# work.net
KiCad netlist of a schematic drawn in EAGLE
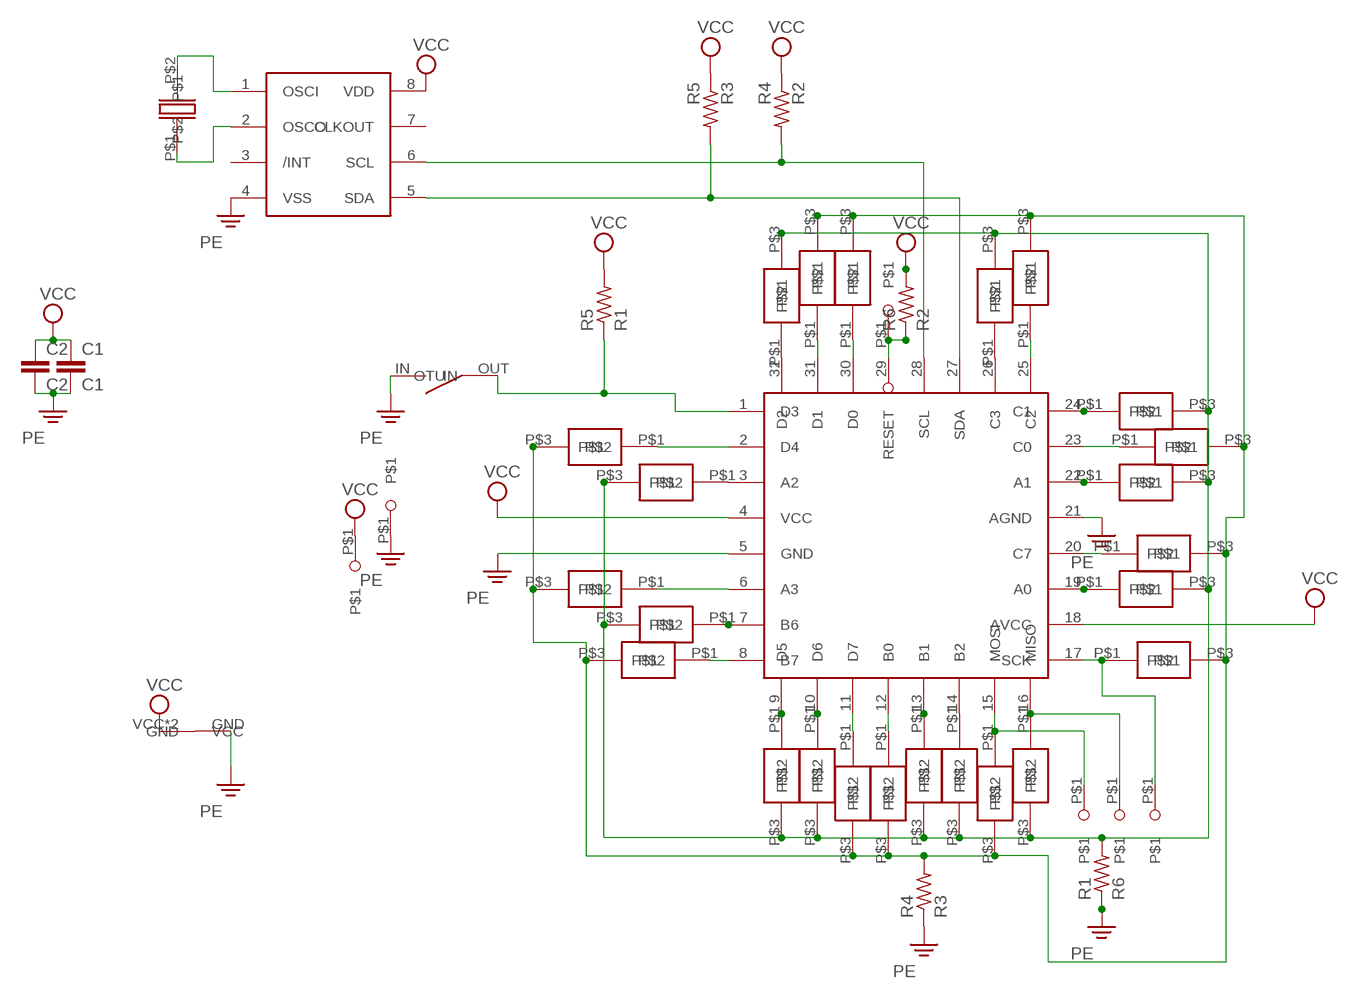
[diagram p0: schematic, sheet 1]

(export (version "E")
  (design (tool "Eeschema 10.0.6"))
  (components
    (comp (ref "C1")
      (value "C1")
      (footprint "eagle-import:C0805K")
      (libsource (lib "eagle-import") (part "C-EUC0805K"))
    )
    (comp (ref "C2")
      (value "C2")
      (footprint "eagle-import:C0805K")
      (libsource (lib "eagle-import") (part "C-EUC0805K"))
    )
    (comp (ref "R1")
      (value "R6")
      (footprint "eagle-import:R0805")
      (libsource (lib "eagle-import") (part "R-US_R0805"))
    )
    (comp (ref "R2")
      (value "R4")
      (footprint "eagle-import:R0805")
      (libsource (lib "eagle-import") (part "R-US_R0805"))
    )
    (comp (ref "R3")
      (value "R5")
      (footprint "eagle-import:R0805")
      (libsource (lib "eagle-import") (part "R-US_R0805"))
    )
    (comp (ref "R4")
      (value "R3")
      (footprint "eagle-import:R0805")
      (libsource (lib "eagle-import") (part "R-US_R0805"))
    )
    (comp (ref "R5")
      (value "R1")
      (footprint "eagle-import:R0805")
      (libsource (lib "eagle-import") (part "R-US_R0805"))
    )
    (comp (ref "R6")
      (value "R2")
      (footprint "eagle-import:R0805")
      (libsource (lib "eagle-import") (part "R-US_R0805"))
    )
    (comp (ref "U$1")
      (value "SMDLED")
      (footprint "eagle-import:SMDLED")
      (libsource (lib "eagle-import") (part "SMDLED"))
    )
    (comp (ref "U$2")
      (value "SMDLED")
      (footprint "eagle-import:SMDLED")
      (libsource (lib "eagle-import") (part "SMDLED"))
    )
    (comp (ref "U$3")
      (value "SMDLED")
      (footprint "eagle-import:SMDLED")
      (libsource (lib "eagle-import") (part "SMDLED"))
    )
    (comp (ref "U$4")
      (value "SMDLED")
      (footprint "eagle-import:SMDLED")
      (libsource (lib "eagle-import") (part "SMDLED"))
    )
    (comp (ref "U$5")
      (value "SMDLED")
      (footprint "eagle-import:SMDLED")
      (libsource (lib "eagle-import") (part "SMDLED"))
    )
    (comp (ref "U$6")
      (value "SMDLED")
      (footprint "eagle-import:SMDLED")
      (libsource (lib "eagle-import") (part "SMDLED"))
    )
    (comp (ref "U$7")
      (value "SMDLED")
      (footprint "eagle-import:SMDLED")
      (libsource (lib "eagle-import") (part "SMDLED"))
    )
    (comp (ref "U$8")
      (value "SMDLED")
      (footprint "eagle-import:SMDLED")
      (libsource (lib "eagle-import") (part "SMDLED"))
    )
    (comp (ref "U$9")
      (value "SMDLED")
      (footprint "eagle-import:SMDLED")
      (libsource (lib "eagle-import") (part "SMDLED"))
    )
    (comp (ref "U$10")
      (value "SMDLED")
      (footprint "eagle-import:SMDLED")
      (libsource (lib "eagle-import") (part "SMDLED"))
    )
    (comp (ref "U$11")
      (value "SMDLED")
      (footprint "eagle-import:SMDLED")
      (libsource (lib "eagle-import") (part "SMDLED"))
    )
    (comp (ref "U$12")
      (value "SMDLED")
      (footprint "eagle-import:SMDLED")
      (libsource (lib "eagle-import") (part "SMDLED"))
    )
    (comp (ref "U$13")
      (value "SMDLED")
      (footprint "eagle-import:SMDLED")
      (libsource (lib "eagle-import") (part "SMDLED"))
    )
    (comp (ref "U$14")
      (value "SMDLED")
      (footprint "eagle-import:SMDLED")
      (libsource (lib "eagle-import") (part "SMDLED"))
    )
    (comp (ref "U$15")
      (value "SMDLED")
      (footprint "eagle-import:SMDLED")
      (libsource (lib "eagle-import") (part "SMDLED"))
    )
    (comp (ref "U$16")
      (value "SMDLED")
      (footprint "eagle-import:SMDLED")
      (libsource (lib "eagle-import") (part "SMDLED"))
    )
    (comp (ref "U$17")
      (value "SMDLED")
      (footprint "eagle-import:SMDLED")
      (libsource (lib "eagle-import") (part "SMDLED"))
    )
    (comp (ref "U$18")
      (value "SMDLED")
      (footprint "eagle-import:SMDLED")
      (libsource (lib "eagle-import") (part "SMDLED"))
    )
    (comp (ref "U$19")
      (value "SMDLED")
      (footprint "eagle-import:SMDLED")
      (libsource (lib "eagle-import") (part "SMDLED"))
    )
    (comp (ref "U$20")
      (value "SMDLED")
      (footprint "eagle-import:SMDLED")
      (libsource (lib "eagle-import") (part "SMDLED"))
    )
    (comp (ref "U$21")
      (value "SMDLED")
      (footprint "eagle-import:SMDLED")
      (libsource (lib "eagle-import") (part "SMDLED"))
    )
    (comp (ref "U$22")
      (value "SMDLED")
      (footprint "eagle-import:SMDLED")
      (libsource (lib "eagle-import") (part "SMDLED"))
    )
    (comp (ref "U$23")
      (value "SMDLED")
      (footprint "eagle-import:SMDLED")
      (libsource (lib "eagle-import") (part "SMDLED"))
    )
    (comp (ref "U$24")
      (value "SMDLED")
      (footprint "eagle-import:SMDLED")
      (libsource (lib "eagle-import") (part "SMDLED"))
    )
    (comp (ref "U$25")
      (value "ATTINY88")
      (footprint "eagle-import:32-TQFT")
      (libsource (lib "eagle-import") (part "ATTINY88"))
    )
    (comp (ref "U$26")
      (value "PAD50")
      (footprint "eagle-import:PAD50")
      (libsource (lib "eagle-import") (part "PAD50"))
    )
    (comp (ref "U$27")
      (value "BAT2009")
      (footprint "eagle-import:BAT2009")
      (libsource (lib "eagle-import") (part "BAT2009"))
    )
    (comp (ref "U$28")
      (value "INT2")
      (footprint "eagle-import:INT2")
      (libsource (lib "eagle-import") (part "INT2"))
    )
    (comp (ref "U$29")
      (value "SMDCRYSTAL")
      (footprint "eagle-import:SMDCRYSTAL")
      (libsource (lib "eagle-import") (part "SMDCRYSTAL"))
    )
    (comp (ref "U$30")
      (value "RTC-SOIC")
      (footprint "eagle-import:8-SOIC")
      (libsource (lib "eagle-import") (part "RTC-SOIC"))
    )
    (comp (ref "U$31")
      (value "PAD50")
      (footprint "eagle-import:PAD50")
      (libsource (lib "eagle-import") (part "PAD50"))
    )
    (comp (ref "U$32")
      (value "PAD50")
      (footprint "eagle-import:PAD50")
      (libsource (lib "eagle-import") (part "PAD50"))
    )
    (comp (ref "U$33")
      (value "PAD50")
      (footprint "eagle-import:PAD50")
      (libsource (lib "eagle-import") (part "PAD50"))
    )
    (comp (ref "U$34")
      (value "PAD50")
      (footprint "eagle-import:PAD50")
      (libsource (lib "eagle-import") (part "PAD50"))
    )
    (comp (ref "U$35")
      (value "PAD50")
      (footprint "eagle-import:PAD50")
      (libsource (lib "eagle-import") (part "PAD50"))
    )
  )
  (nets
    (net (code "1") (name "Net-(U$1-P$2)") (class "Default")
      (node (ref "R4") (pin "2") (pinfunction "2_2") (pintype "passive"))
      (node (ref "U$1") (pin "P$3") (pinfunction "P$2_P$3") (pintype "bidirectional"))
      (node (ref "U$10") (pin "P$3") (pinfunction "P$2_P$3") (pintype "bidirectional"))
      (node (ref "U$11") (pin "P$3") (pinfunction "P$2_P$3") (pintype "bidirectional"))
      (node (ref "U$13") (pin "P$3") (pinfunction "P$2_P$3") (pintype "bidirectional"))
      (node (ref "U$15") (pin "P$3") (pinfunction "P$2_P$3") (pintype "bidirectional"))
      (node (ref "U$17") (pin "P$3") (pinfunction "P$2_P$3") (pintype "bidirectional"))
      (node (ref "U$20") (pin "P$3") (pinfunction "P$2_P$3") (pintype "bidirectional"))
      (node (ref "U$22") (pin "P$3") (pinfunction "P$2_P$3") (pintype "bidirectional"))
      (node (ref "U$23") (pin "P$3") (pinfunction "P$2_P$3") (pintype "bidirectional"))
      (node (ref "U$4") (pin "P$3") (pinfunction "P$2_P$3") (pintype "bidirectional"))
      (node (ref "U$8") (pin "P$3") (pinfunction "P$2_P$3") (pintype "bidirectional"))
      (node (ref "U$9") (pin "P$3") (pinfunction "P$2_P$3") (pintype "bidirectional"))
    )
    (net (code "2") (name "Net-(U$12-P$2)") (class "Default")
      (node (ref "R1") (pin "2") (pinfunction "2_2") (pintype "passive"))
      (node (ref "U$12") (pin "P$3") (pinfunction "P$2_P$3") (pintype "bidirectional"))
      (node (ref "U$14") (pin "P$3") (pinfunction "P$2_P$3") (pintype "bidirectional"))
      (node (ref "U$16") (pin "P$3") (pinfunction "P$2_P$3") (pintype "bidirectional"))
      (node (ref "U$18") (pin "P$3") (pinfunction "P$2_P$3") (pintype "bidirectional"))
      (node (ref "U$19") (pin "P$3") (pinfunction "P$2_P$3") (pintype "bidirectional"))
      (node (ref "U$2") (pin "P$3") (pinfunction "P$2_P$3") (pintype "bidirectional"))
      (node (ref "U$21") (pin "P$3") (pinfunction "P$2_P$3") (pintype "bidirectional"))
      (node (ref "U$24") (pin "P$3") (pinfunction "P$2_P$3") (pintype "bidirectional"))
      (node (ref "U$3") (pin "P$3") (pinfunction "P$2_P$3") (pintype "bidirectional"))
      (node (ref "U$5") (pin "P$3") (pinfunction "P$2_P$3") (pintype "bidirectional"))
      (node (ref "U$6") (pin "P$3") (pinfunction "P$2_P$3") (pintype "bidirectional"))
      (node (ref "U$7") (pin "P$3") (pinfunction "P$2_P$3") (pintype "bidirectional"))
    )
    (net (code "3") (name "Net-(U$25-A0)") (class "Default")
      (node (ref "U$12") (pin "P$1") (pinfunction "P$1_P$1") (pintype "bidirectional"))
      (node (ref "U$25") (pin "19") (pinfunction "A0_19") (pintype "bidirectional"))
    )
    (net (code "4") (name "Net-(U$25-A1)") (class "Default")
      (node (ref "U$21") (pin "P$1") (pinfunction "P$1_P$1") (pintype "bidirectional"))
      (node (ref "U$25") (pin "22") (pinfunction "A1_22") (pintype "bidirectional"))
    )
    (net (code "5") (name "Net-(U$25-A2)") (class "Default")
      (node (ref "U$16") (pin "P$1") (pinfunction "P$1_P$1") (pintype "bidirectional"))
      (node (ref "U$25") (pin "3") (pinfunction "A2_3") (pintype "bidirectional"))
    )
    (net (code "6") (name "Net-(U$25-A3)") (class "Default")
      (node (ref "U$17") (pin "P$1") (pinfunction "P$1_P$1") (pintype "bidirectional"))
      (node (ref "U$25") (pin "6") (pinfunction "A3_6") (pintype "bidirectional"))
    )
    (net (code "7") (name "Net-(U$25-B0)") (class "Default")
      (node (ref "U$1") (pin "P$1") (pinfunction "P$1_P$1") (pintype "bidirectional"))
      (node (ref "U$25") (pin "12") (pinfunction "B0_12") (pintype "bidirectional"))
    )
    (net (code "8") (name "Net-(U$25-B1)") (class "Default")
      (node (ref "U$2") (pin "P$1") (pinfunction "P$1_P$1") (pintype "bidirectional"))
      (node (ref "U$25") (pin "13") (pinfunction "B1_13") (pintype "bidirectional"))
    )
    (net (code "9") (name "Net-(U$25-B2)") (class "Default")
      (node (ref "U$25") (pin "14") (pinfunction "B2_14") (pintype "bidirectional"))
      (node (ref "U$3") (pin "P$1") (pinfunction "P$1_P$1") (pintype "bidirectional"))
    )
    (net (code "10") (name "Net-(U$25-B6)") (class "Default")
      (node (ref "U$25") (pin "7") (pinfunction "B6_7") (pintype "bidirectional"))
      (node (ref "U$7") (pin "P$1") (pinfunction "P$1_P$1") (pintype "bidirectional"))
    )
    (net (code "11") (name "Net-(U$25-B7)") (class "Default")
      (node (ref "U$25") (pin "8") (pinfunction "B7_8") (pintype "bidirectional"))
      (node (ref "U$8") (pin "P$1") (pinfunction "P$1_P$1") (pintype "bidirectional"))
    )
    (net (code "12") (name "Net-(U$25-C0)") (class "Default")
      (node (ref "U$22") (pin "P$1") (pinfunction "P$1_P$1") (pintype "bidirectional"))
      (node (ref "U$25") (pin "23") (pinfunction "C0_23") (pintype "bidirectional"))
    )
    (net (code "13") (name "Net-(U$25-C1)") (class "Default")
      (node (ref "U$25") (pin "24") (pinfunction "C1_24") (pintype "bidirectional"))
      (node (ref "U$6") (pin "P$1") (pinfunction "P$1_P$1") (pintype "bidirectional"))
    )
    (net (code "14") (name "Net-(U$25-C2)") (class "Default")
      (node (ref "U$25") (pin "25") (pinfunction "C2_25") (pintype "bidirectional"))
      (node (ref "U$9") (pin "P$1") (pinfunction "P$1_P$1") (pintype "bidirectional"))
    )
    (net (code "15") (name "Net-(U$25-C3)") (class "Default")
      (node (ref "U$24") (pin "P$1") (pinfunction "P$1_P$1") (pintype "bidirectional"))
      (node (ref "U$25") (pin "26") (pinfunction "C3_26") (pintype "bidirectional"))
    )
    (net (code "16") (name "Net-(U$25-C7)") (class "Default")
      (node (ref "U$10") (pin "P$1") (pinfunction "P$1_P$1") (pintype "bidirectional"))
      (node (ref "U$25") (pin "20") (pinfunction "C7_20") (pintype "bidirectional"))
    )
    (net (code "17") (name "Net-(U$25-D0)") (class "Default")
      (node (ref "U$23") (pin "P$1") (pinfunction "P$1_P$1") (pintype "bidirectional"))
      (node (ref "U$25") (pin "30") (pinfunction "D0_30") (pintype "bidirectional"))
    )
    (net (code "18") (name "Net-(U$25-D1)") (class "Default")
      (node (ref "U$13") (pin "P$1") (pinfunction "P$1_P$1") (pintype "bidirectional"))
      (node (ref "U$25") (pin "31") (pinfunction "D1_31") (pintype "bidirectional"))
    )
    (net (code "19") (name "Net-(U$25-D2)") (class "Default")
      (node (ref "U$14") (pin "P$1") (pinfunction "P$1_P$1") (pintype "bidirectional"))
      (node (ref "U$25") (pin "32") (pinfunction "D2_32") (pintype "bidirectional"))
    )
    (net (code "20") (name "Net-(U$25-D3)") (class "Default")
      (node (ref "R5") (pin "1") (pinfunction "1_1") (pintype "passive"))
      (node (ref "U$25") (pin "1") (pinfunction "D3_1") (pintype "bidirectional"))
      (node (ref "U$28") (pin "OUT") (pinfunction "OTU_OUT") (pintype "bidirectional"))
    )
    (net (code "21") (name "Net-(U$25-D4)") (class "Default")
      (node (ref "U$15") (pin "P$1") (pinfunction "P$1_P$1") (pintype "bidirectional"))
      (node (ref "U$25") (pin "2") (pinfunction "D4_2") (pintype "bidirectional"))
    )
    (net (code "22") (name "Net-(U$25-D5)") (class "Default")
      (node (ref "U$18") (pin "P$1") (pinfunction "P$1_P$1") (pintype "bidirectional"))
      (node (ref "U$25") (pin "9") (pinfunction "D5_9") (pintype "bidirectional"))
    )
    (net (code "23") (name "Net-(U$25-D6)") (class "Default")
      (node (ref "U$19") (pin "P$1") (pinfunction "P$1_P$1") (pintype "bidirectional"))
      (node (ref "U$25") (pin "10") (pinfunction "D6_10") (pintype "bidirectional"))
    )
    (net (code "24") (name "Net-(U$25-D7)") (class "Default")
      (node (ref "U$20") (pin "P$1") (pinfunction "P$1_P$1") (pintype "bidirectional"))
      (node (ref "U$25") (pin "11") (pinfunction "D7_11") (pintype "bidirectional"))
    )
    (net (code "25") (name "Net-(U$25-MISO)") (class "Default")
      (node (ref "U$25") (pin "16") (pinfunction "MISO_16") (pintype "bidirectional"))
      (node (ref "U$31") (pin "P$1") (pinfunction "P$1_P$1") (pintype "bidirectional"))
      (node (ref "U$5") (pin "P$1") (pinfunction "P$1_P$1") (pintype "bidirectional"))
    )
    (net (code "26") (name "Net-(U$25-MOSI)") (class "Default")
      (node (ref "U$25") (pin "15") (pinfunction "MOSI_15") (pintype "bidirectional"))
      (node (ref "U$32") (pin "P$1") (pinfunction "P$1_P$1") (pintype "bidirectional"))
      (node (ref "U$4") (pin "P$1") (pinfunction "P$1_P$1") (pintype "bidirectional"))
    )
    (net (code "27") (name "Net-(U$25-RESET)") (class "Default")
      (node (ref "R6") (pin "1") (pinfunction "1_1") (pintype "passive"))
      (node (ref "U$25") (pin "29") (pinfunction "RESET_29") (pintype "input"))
      (node (ref "U$26") (pin "P$1") (pinfunction "P$1_P$1") (pintype "bidirectional"))
    )
    (net (code "28") (name "Net-(U$25-SCK)") (class "Default")
      (node (ref "U$11") (pin "P$1") (pinfunction "P$1_P$1") (pintype "bidirectional"))
      (node (ref "U$25") (pin "17") (pinfunction "SCK_17") (pintype "bidirectional"))
      (node (ref "U$33") (pin "P$1") (pinfunction "P$1_P$1") (pintype "bidirectional"))
    )
    (net (code "29") (name "Net-(U$25-SCL)") (class "Default")
      (node (ref "R2") (pin "2") (pinfunction "2_2") (pintype "passive"))
      (node (ref "U$25") (pin "28") (pinfunction "SCL_28") (pintype "bidirectional"))
      (node (ref "U$30") (pin "6") (pinfunction "SCL_6") (pintype "input"))
    )
    (net (code "30") (name "Net-(U$25-SDA)") (class "Default")
      (node (ref "R3") (pin "2") (pinfunction "2_2") (pintype "passive"))
      (node (ref "U$25") (pin "27") (pinfunction "SDA_27") (pintype "bidirectional"))
      (node (ref "U$30") (pin "5") (pinfunction "SDA_5") (pintype "bidirectional"))
    )
    (net (code "31") (name "Net-(U$30-OSCI)") (class "Default")
      (node (ref "U$29") (pin "P$2") (pinfunction "P$2_P$2") (pintype "bidirectional"))
      (node (ref "U$30") (pin "1") (pinfunction "OSCI_1") (pintype "input"))
    )
    (net (code "32") (name "Net-(U$30-OSCO)") (class "Default")
      (node (ref "U$29") (pin "P$1") (pinfunction "P$1_P$1") (pintype "bidirectional"))
      (node (ref "U$30") (pin "2") (pinfunction "OSCO_2") (pintype "output"))
    )
    (net (code "33") (name "PE") (class "Default")
      (node (ref "C1") (pin "2") (pinfunction "2_2") (pintype "passive"))
      (node (ref "C2") (pin "2") (pinfunction "2_2") (pintype "passive"))
      (node (ref "R1") (pin "1") (pinfunction "1_1") (pintype "passive"))
      (node (ref "R4") (pin "1") (pinfunction "1_1") (pintype "passive"))
      (node (ref "U$25") (pin "21") (pinfunction "AGND_21") (pintype "power_in"))
      (node (ref "U$25") (pin "5") (pinfunction "GND_5") (pintype "power_in"))
      (node (ref "U$27") (pin "GND") (pinfunction "GND_GND") (pintype "bidirectional"))
      (node (ref "U$28") (pin "IN") (pinfunction "IN_IN") (pintype "bidirectional"))
      (node (ref "U$30") (pin "4") (pinfunction "VSS_4") (pintype "power_in"))
      (node (ref "U$34") (pin "P$1") (pinfunction "P$1_P$1") (pintype "bidirectional"))
    )
    (net (code "34") (name "VCC") (class "Default")
      (node (ref "C1") (pin "1") (pinfunction "1_1") (pintype "passive"))
      (node (ref "C2") (pin "1") (pinfunction "1_1") (pintype "passive"))
      (node (ref "R2") (pin "1") (pinfunction "1_1") (pintype "passive"))
      (node (ref "R3") (pin "1") (pinfunction "1_1") (pintype "passive"))
      (node (ref "R5") (pin "2") (pinfunction "2_2") (pintype "passive"))
      (node (ref "R6") (pin "2") (pinfunction "2_2") (pintype "passive"))
      (node (ref "U$25") (pin "18") (pinfunction "AVCC_18") (pintype "power_in"))
      (node (ref "U$25") (pin "4") (pinfunction "VCC_4") (pintype "power_in"))
      (node (ref "U$27") (pin "VCC") (pinfunction "VCC_VCC") (pintype "bidirectional"))
      (node (ref "U$27") (pin "VCC2") (pinfunction "VCC_VCC2") (pintype "bidirectional"))
      (node (ref "U$30") (pin "8") (pinfunction "VDD_8") (pintype "power_in"))
      (node (ref "U$35") (pin "P$1") (pinfunction "P$1_P$1") (pintype "bidirectional"))
    )
    (net (code "35") (name "unconnected-(U$30-CLKOUT-Pad7)") (class "Default")
      (node (ref "U$30") (pin "7") (pinfunction "CLKOUT_7") (pintype "output"))
    )
    (net (code "36") (name "unconnected-(U$30-{slash}INT-Pad3)") (class "Default")
      (node (ref "U$30") (pin "3") (pinfunction "/INT_3") (pintype "output"))
    )
  )
)
